# ChronoCape.net
KiCad netlist of a schematic drawn in EAGLE
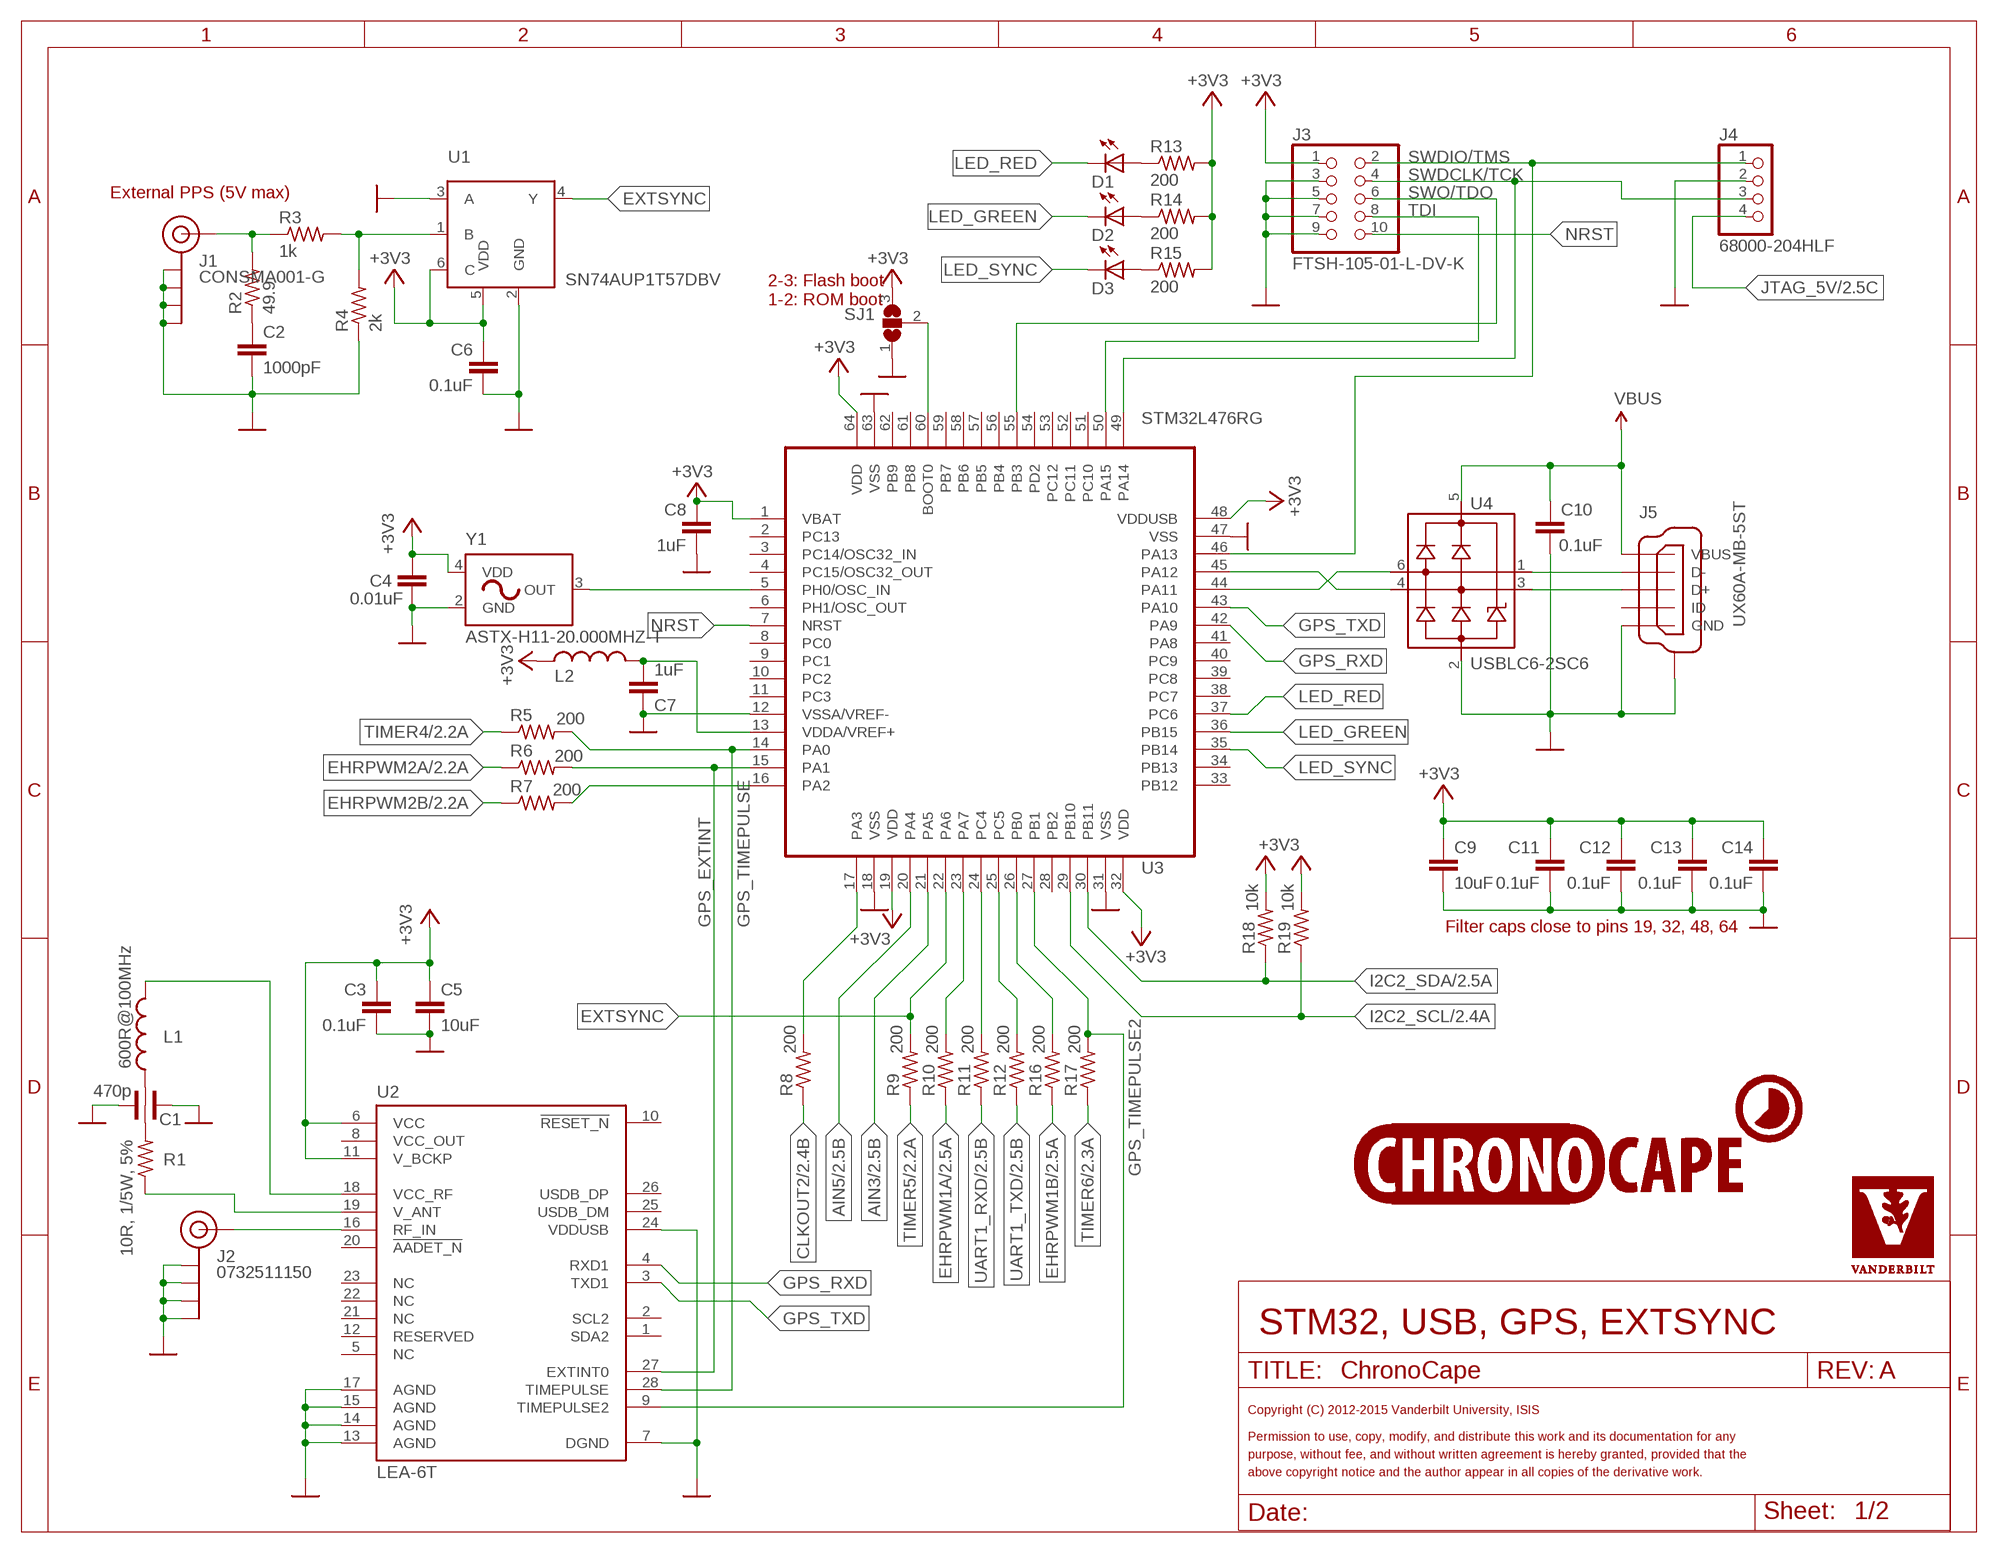
[diagram p0: schematic, sheet 1]
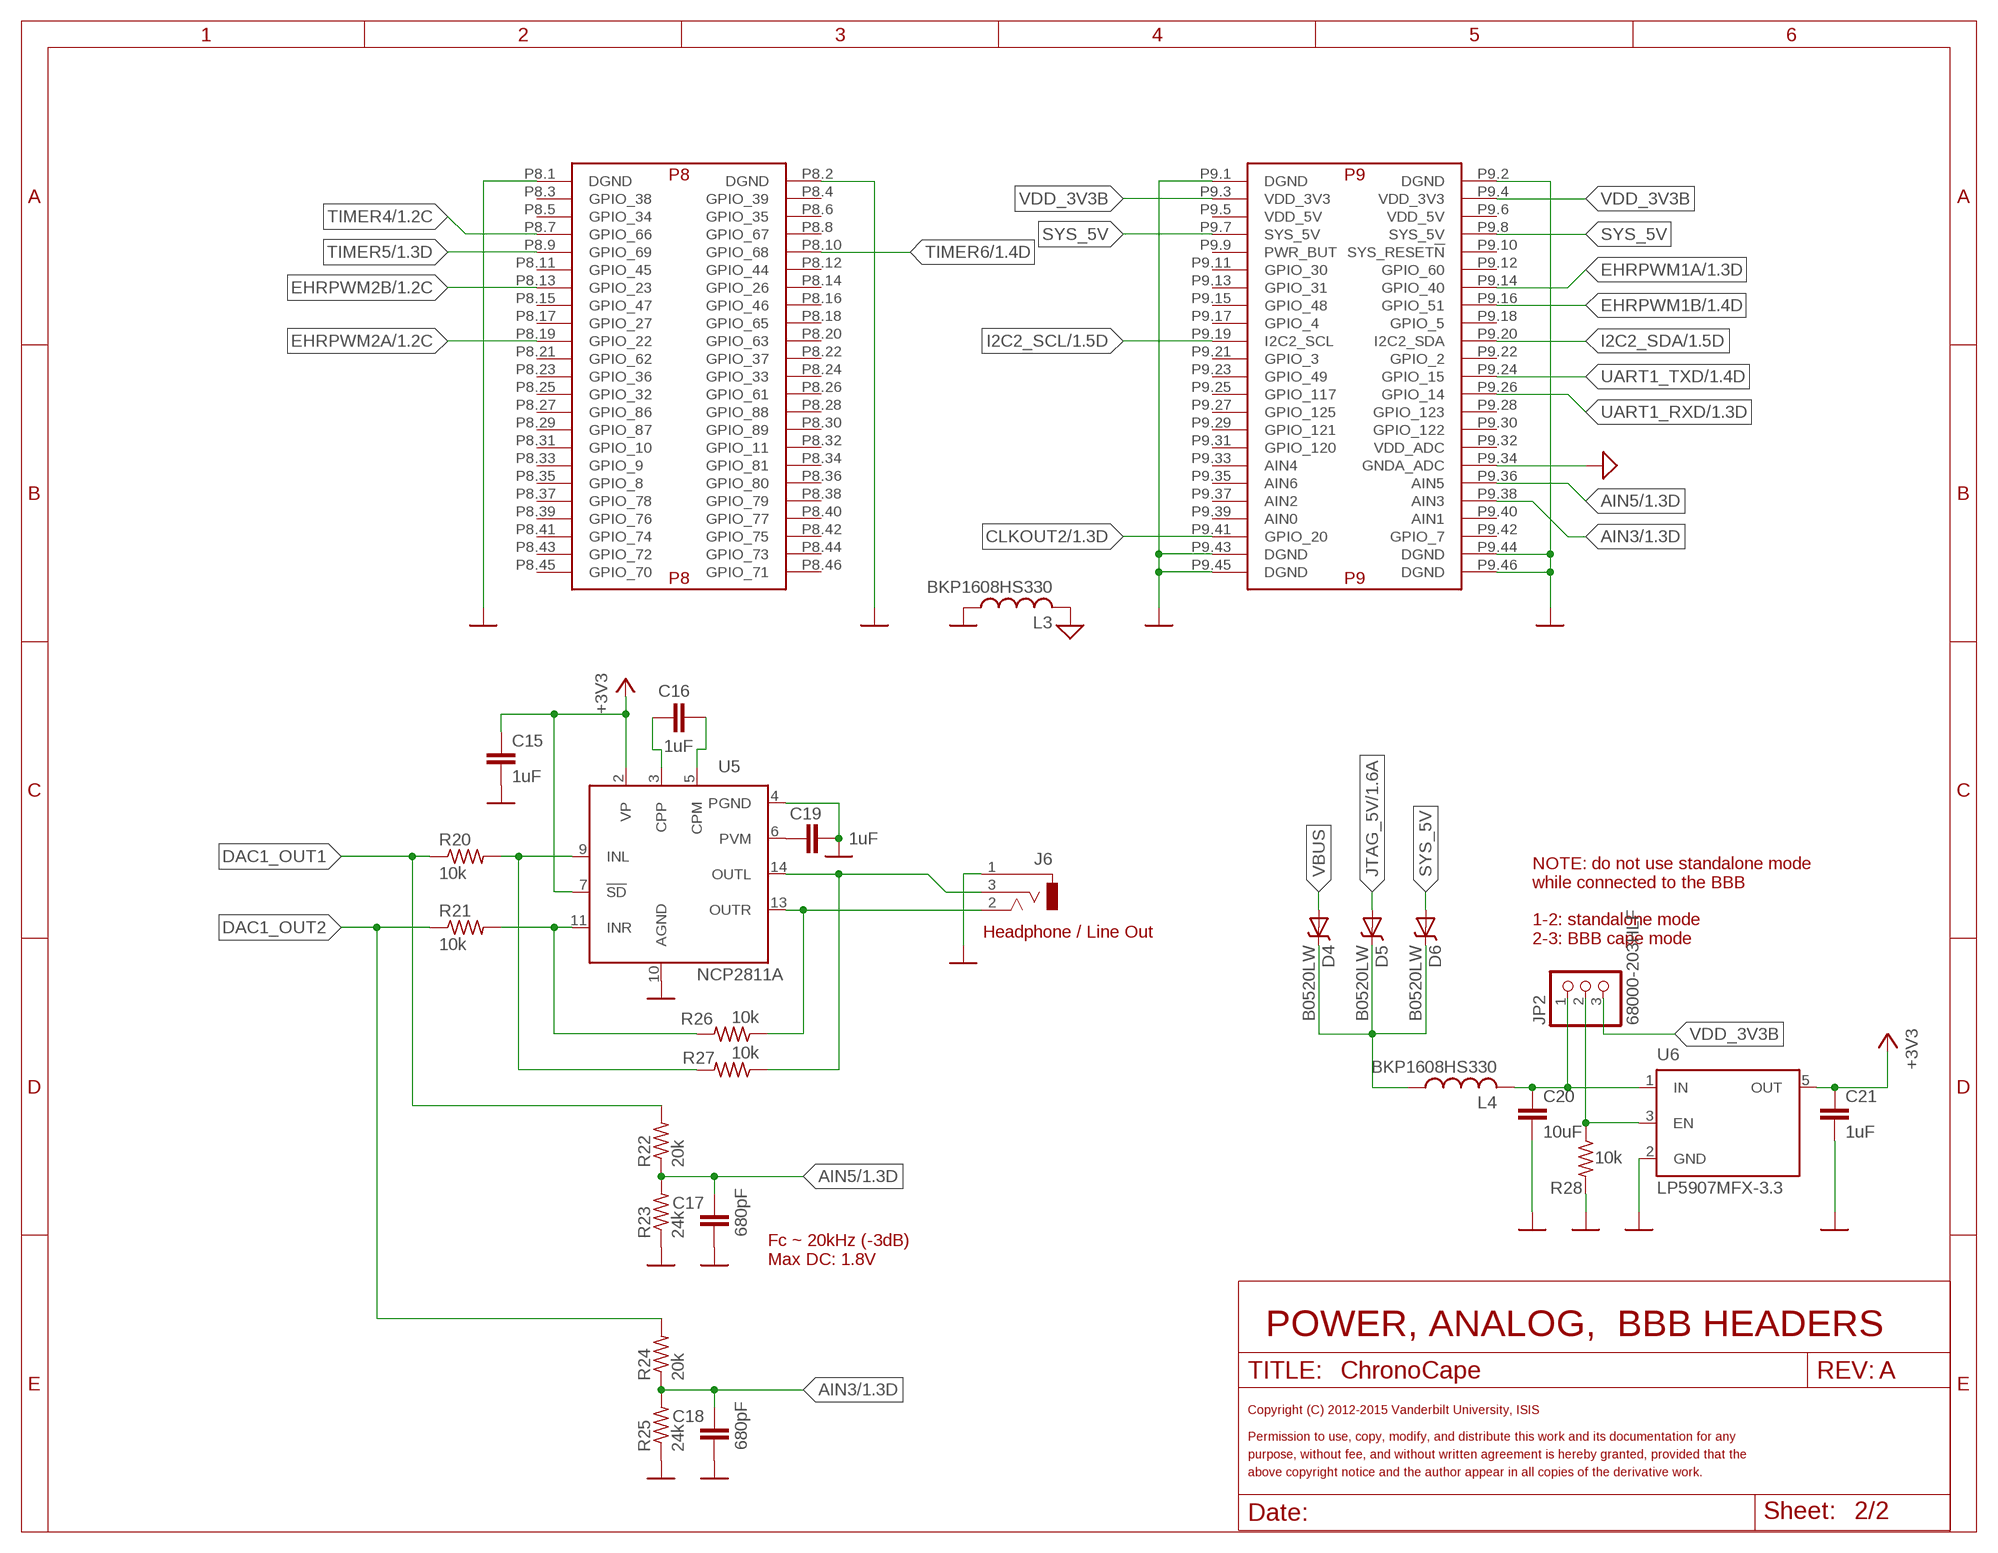
[diagram p1: schematic, sheet 2]

(export (version "E")
  (design (tool "Eeschema 10.0.6"))
  (components
    (comp (ref "C1")
      (value "470p")
      (footprint "eagle-import:CTHROUGH0805")
      (libsource (lib "eagle-import") (part "CTHROUGH0805"))
    )
    (comp (ref "C2")
      (value "1000pF")
      (footprint "eagle-import:CHIP0603")
      (libsource (lib "eagle-import") (part "C0603"))
    )
    (comp (ref "C3")
      (value "0.1uF")
      (footprint "eagle-import:CHIP0603")
      (libsource (lib "eagle-import") (part "C0603"))
    )
    (comp (ref "C4")
      (value "0.01uF")
      (footprint "eagle-import:CHIP0603")
      (libsource (lib "eagle-import") (part "C0603"))
    )
    (comp (ref "C5")
      (value "10uF")
      (footprint "eagle-import:CHIP0805")
      (libsource (lib "eagle-import") (part "C0805"))
    )
    (comp (ref "C6")
      (value "0.1uF")
      (footprint "eagle-import:CHIP0603")
      (libsource (lib "eagle-import") (part "C0603"))
    )
    (comp (ref "C7")
      (value "1uF")
      (footprint "eagle-import:CHIP0603")
      (libsource (lib "eagle-import") (part "C0603"))
    )
    (comp (ref "C8")
      (value "1uF")
      (footprint "eagle-import:CHIP0603")
      (libsource (lib "eagle-import") (part "C0603"))
    )
    (comp (ref "C9")
      (value "10uF")
      (footprint "eagle-import:CHIP0805")
      (libsource (lib "eagle-import") (part "C0805"))
    )
    (comp (ref "C10")
      (value "0.1uF")
      (footprint "eagle-import:CHIP0603")
      (libsource (lib "eagle-import") (part "C0603"))
    )
    (comp (ref "C11")
      (value "0.1uF")
      (footprint "eagle-import:CHIP0603")
      (libsource (lib "eagle-import") (part "C0603"))
    )
    (comp (ref "C12")
      (value "0.1uF")
      (footprint "eagle-import:CHIP0603")
      (libsource (lib "eagle-import") (part "C0603"))
    )
    (comp (ref "C13")
      (value "0.1uF")
      (footprint "eagle-import:CHIP0603")
      (libsource (lib "eagle-import") (part "C0603"))
    )
    (comp (ref "C14")
      (value "0.1uF")
      (footprint "eagle-import:CHIP0603")
      (libsource (lib "eagle-import") (part "C0603"))
    )
    (comp (ref "D1")
      (value "598-8010-107F")
      (footprint "eagle-import:D0603")
      (libsource (lib "eagle-import") (part "LED0603"))
    )
    (comp (ref "D2")
      (value "598-8070-107F")
      (footprint "eagle-import:D0603")
      (libsource (lib "eagle-import") (part "LED0603"))
    )
    (comp (ref "D3")
      (value "598-8030-107F")
      (footprint "eagle-import:D0603")
      (libsource (lib "eagle-import") (part "LED0603"))
    )
    (comp (ref "J1")
      (value "CONSMA001-G")
      (footprint "eagle-import:SMA-THROUGH")
      (libsource (lib "eagle-import") (part "SMA_THROUGH"))
    )
    (comp (ref "J2")
      (value "0732511150")
      (footprint "eagle-import:SMA-EDGE")
      (libsource (lib "eagle-import") (part "SMA_EDGE"))
    )
    (comp (ref "J3")
      (value "FTSH-105-01-L-DV-K")
      (footprint "eagle-import:FTSH-105-01-L-DV-K")
      (libsource (lib "eagle-import") (part "FTSH-105-01-L-DV-K"))
    )
    (comp (ref "J4")
      (value "68000-204HLF")
      (footprint "eagle-import:1X04")
      (libsource (lib "eagle-import") (part "PINHD-1X4"))
    )
    (comp (ref "J5")
      (value "UX60A-MB-5ST")
      (footprint "eagle-import:UX60A-MB-5ST")
      (libsource (lib "eagle-import") (part "UX60A-MB-5ST"))
    )
    (comp (ref "L1")
      (value "600R@100MHz")
      (footprint "eagle-import:CHIP0603")
      (libsource (lib "eagle-import") (part "L0603"))
    )
    (comp (ref "L2")
      (value "BKP1608HS330")
      (footprint "eagle-import:CHIP0603")
      (libsource (lib "eagle-import") (part "L0603"))
    )
    (comp (ref "LOGO1")
      (value "LOGO_CHRONOCAPE")
      (footprint "eagle-import:LOGO_CHRONOSCAPE")
      (libsource (lib "eagle-import") (part "LOGO_CHRONOCAPE"))
    )
    (comp (ref "LOGO2")
      (value "LOGO_VANDERBILT280MIL")
      (footprint "eagle-import:LOGO_VANDERBILT_280MIL")
      (libsource (lib "eagle-import") (part "LOGO_VANDERBILT280MIL"))
    )
    (comp (ref "R1")
      (value "10R, 1/5W, 5%")
      (footprint "eagle-import:CHIP0603")
      (libsource (lib "eagle-import") (part "R0603"))
    )
    (comp (ref "R2")
      (value "49.9")
      (footprint "eagle-import:CHIP0603")
      (libsource (lib "eagle-import") (part "R0603"))
    )
    (comp (ref "R3")
      (value "1k")
      (footprint "eagle-import:CHIP0603")
      (libsource (lib "eagle-import") (part "R0603"))
    )
    (comp (ref "R4")
      (value "2k")
      (footprint "eagle-import:CHIP0603")
      (libsource (lib "eagle-import") (part "R0603"))
    )
    (comp (ref "R5")
      (value "200")
      (footprint "eagle-import:CHIP0603")
      (libsource (lib "eagle-import") (part "R0603"))
    )
    (comp (ref "R6")
      (value "200")
      (footprint "eagle-import:CHIP0603")
      (libsource (lib "eagle-import") (part "R0603"))
    )
    (comp (ref "R7")
      (value "200")
      (footprint "eagle-import:CHIP0603")
      (libsource (lib "eagle-import") (part "R0603"))
    )
    (comp (ref "R8")
      (value "200")
      (footprint "eagle-import:CHIP0603")
      (libsource (lib "eagle-import") (part "R0603"))
    )
    (comp (ref "R9")
      (value "200")
      (footprint "eagle-import:CHIP0603")
      (libsource (lib "eagle-import") (part "R0603"))
    )
    (comp (ref "R10")
      (value "200")
      (footprint "eagle-import:CHIP0603")
      (libsource (lib "eagle-import") (part "R0603"))
    )
    (comp (ref "R11")
      (value "200")
      (footprint "eagle-import:CHIP0603")
      (libsource (lib "eagle-import") (part "R0603"))
    )
    (comp (ref "R12")
      (value "200")
      (footprint "eagle-import:CHIP0603")
      (libsource (lib "eagle-import") (part "R0603"))
    )
    (comp (ref "R13")
      (value "200")
      (footprint "eagle-import:CHIP0603")
      (libsource (lib "eagle-import") (part "R0603"))
    )
    (comp (ref "R14")
      (value "200")
      (footprint "eagle-import:CHIP0603")
      (libsource (lib "eagle-import") (part "R0603"))
    )
    (comp (ref "R15")
      (value "200")
      (footprint "eagle-import:CHIP0603")
      (libsource (lib "eagle-import") (part "R0603"))
    )
    (comp (ref "R16")
      (value "200")
      (footprint "eagle-import:CHIP0603")
      (libsource (lib "eagle-import") (part "R0603"))
    )
    (comp (ref "R17")
      (value "200")
      (footprint "eagle-import:CHIP0603")
      (libsource (lib "eagle-import") (part "R0603"))
    )
    (comp (ref "R18")
      (value "10k")
      (footprint "eagle-import:CHIP0603")
      (libsource (lib "eagle-import") (part "R0603"))
    )
    (comp (ref "R19")
      (value "10k")
      (footprint "eagle-import:CHIP0603")
      (libsource (lib "eagle-import") (part "R0603"))
    )
    (comp (ref "SJ1")
      (value "SOLDERJUMPER_2WAYPASTE1&2")
      (footprint "eagle-import:SJ_3_PASTE1&2")
      (libsource (lib "eagle-import") (part "SOLDERJUMPER_2WAYPASTE1&2"))
    )
    (comp (ref "U1")
      (value "SN74AUP1T57DBV")
      (footprint "eagle-import:SOT23-6")
      (libsource (lib "eagle-import") (part "SN74AUP1T57DBV"))
    )
    (comp (ref "U2")
      (value "LEA-6T")
      (footprint "eagle-import:LEA-6")
      (libsource (lib "eagle-import") (part "LEA-6T"))
    )
    (comp (ref "U3")
      (value "STM32L476RG")
      (footprint "eagle-import:LQFP64")
      (libsource (lib "eagle-import") (part "STM32L476RG"))
    )
    (comp (ref "U4")
      (value "USBLC6-2SC6")
      (footprint "eagle-import:SOT23-6L")
      (fields (field (name "MF") "STMicroelectronics"))
      (libsource (lib "eagle-import") (part "USBLC6-2SC6"))
    )
    (comp (ref "Y1")
      (value "ASTX-H11-20.000MHZ-T")
      (footprint "eagle-import:SMD_3.2X2.5")
      (libsource (lib "eagle-import") (part "OSC_ASTX-H11"))
    )
    (comp (ref "BBB1")
      (value "BEAGLE_BONE_BLACK_CAPE")
      (footprint "eagle-import:BEAGLE_BONE_BLACK_CAPE")
      (libsource (lib "eagle-import") (part "BEAGLE_BONE_BLACK_CAPE"))
    )
    (comp (ref "C15")
      (value "1uF")
      (footprint "eagle-import:CHIP0603")
      (libsource (lib "eagle-import") (part "C0603"))
    )
    (comp (ref "C16")
      (value "1uF")
      (footprint "eagle-import:CHIP0603")
      (libsource (lib "eagle-import") (part "C0603"))
    )
    (comp (ref "C17")
      (value "680pF")
      (footprint "eagle-import:CHIP0603")
      (libsource (lib "eagle-import") (part "C0603"))
    )
    (comp (ref "C18")
      (value "680pF")
      (footprint "eagle-import:CHIP0603")
      (libsource (lib "eagle-import") (part "C0603"))
    )
    (comp (ref "C19")
      (value "1uF")
      (footprint "eagle-import:CHIP0603")
      (libsource (lib "eagle-import") (part "C0603"))
    )
    (comp (ref "C20")
      (value "10uF")
      (footprint "eagle-import:CHIP0805")
      (libsource (lib "eagle-import") (part "C0805"))
    )
    (comp (ref "C21")
      (value "1uF")
      (footprint "eagle-import:CHIP0603")
      (libsource (lib "eagle-import") (part "C0603"))
    )
    (comp (ref "D4")
      (value "B0520LW")
      (footprint "eagle-import:SOD-123")
      (libsource (lib "eagle-import") (part "DIODE-SCHOTTKYSOD-123"))
    )
    (comp (ref "D5")
      (value "B0520LW")
      (footprint "eagle-import:SOD-123")
      (libsource (lib "eagle-import") (part "DIODE-SCHOTTKYSOD-123"))
    )
    (comp (ref "D6")
      (value "B0520LW")
      (footprint "eagle-import:SOD-123")
      (libsource (lib "eagle-import") (part "DIODE-SCHOTTKYSOD-123"))
    )
    (comp (ref "J6")
      (value "CON_STEREO_JACK_SJ-3523-SMT")
      (footprint "eagle-import:SJ-3523-SMT")
      (libsource (lib "eagle-import") (part "CON_STEREO_JACK_SJ-3523-SMT"))
    )
    (comp (ref "JP2")
      (value "68000-203HLF")
      (footprint "eagle-import:1X03")
      (libsource (lib "eagle-import") (part "PINHD-1X3"))
    )
    (comp (ref "L3")
      (value "BKP1608HS330")
      (footprint "eagle-import:CHIP0603")
      (libsource (lib "eagle-import") (part "L0603"))
    )
    (comp (ref "L4")
      (value "BKP1608HS330")
      (footprint "eagle-import:CHIP0603")
      (libsource (lib "eagle-import") (part "L0603"))
    )
    (comp (ref "R20")
      (value "10k")
      (footprint "eagle-import:CHIP0603")
      (libsource (lib "eagle-import") (part "R0603"))
    )
    (comp (ref "R21")
      (value "10k")
      (footprint "eagle-import:CHIP0603")
      (libsource (lib "eagle-import") (part "R0603"))
    )
    (comp (ref "R22")
      (value "20k")
      (footprint "eagle-import:CHIP0603")
      (libsource (lib "eagle-import") (part "R0603"))
    )
    (comp (ref "R23")
      (value "24k")
      (footprint "eagle-import:CHIP0603")
      (libsource (lib "eagle-import") (part "R0603"))
    )
    (comp (ref "R24")
      (value "20k")
      (footprint "eagle-import:CHIP0603")
      (libsource (lib "eagle-import") (part "R0603"))
    )
    (comp (ref "R25")
      (value "24k")
      (footprint "eagle-import:CHIP0603")
      (libsource (lib "eagle-import") (part "R0603"))
    )
    (comp (ref "R26")
      (value "10k")
      (footprint "eagle-import:CHIP0603")
      (libsource (lib "eagle-import") (part "R0603"))
    )
    (comp (ref "R27")
      (value "10k")
      (footprint "eagle-import:CHIP0603")
      (libsource (lib "eagle-import") (part "R0603"))
    )
    (comp (ref "R28")
      (value "10k")
      (footprint "eagle-import:CHIP0603")
      (libsource (lib "eagle-import") (part "R0603"))
    )
    (comp (ref "U5")
      (value "NCP2811A")
      (footprint "eagle-import:TSSOP14")
      (libsource (lib "eagle-import") (part "NCP2811A"))
    )
    (comp (ref "U6")
      (value "LP5907MFX-3.3")
      (footprint "eagle-import:SOT23-5")
      (libsource (lib "eagle-import") (part "LP5907MFX"))
    )
  )
  (nets
    (net (code "1") (name "+3V3") (class "Default")
      (node (ref "C11") (pin "1") (pinfunction "1_1") (pintype "passive"))
      (node (ref "C12") (pin "1") (pinfunction "1_1") (pintype "passive"))
      (node (ref "C13") (pin "1") (pinfunction "1_1") (pintype "passive"))
      (node (ref "C14") (pin "1") (pinfunction "1_1") (pintype "passive"))
      (node (ref "C15") (pin "1") (pinfunction "1_1") (pintype "passive"))
      (node (ref "C21") (pin "1") (pinfunction "1_1") (pintype "passive"))
      (node (ref "C3") (pin "1") (pinfunction "1_1") (pintype "passive"))
      (node (ref "C4") (pin "1") (pinfunction "1_1") (pintype "passive"))
      (node (ref "C5") (pin "1") (pinfunction "1_1") (pintype "passive"))
      (node (ref "C6") (pin "1") (pinfunction "1_1") (pintype "passive"))
      (node (ref "C8") (pin "1") (pinfunction "1_1") (pintype "passive"))
      (node (ref "C9") (pin "1") (pinfunction "1_1") (pintype "passive"))
      (node (ref "J3") (pin "1") (pinfunction "1_1") (pintype "passive"))
      (node (ref "L2") (pin "2") (pinfunction "2_2") (pintype "passive"))
      (node (ref "R13") (pin "2") (pinfunction "2_2") (pintype "passive"))
      (node (ref "R14") (pin "2") (pinfunction "2_2") (pintype "passive"))
      (node (ref "R15") (pin "2") (pinfunction "2_2") (pintype "passive"))
      (node (ref "R18") (pin "2") (pinfunction "2_2") (pintype "passive"))
      (node (ref "R19") (pin "2") (pinfunction "2_2") (pintype "passive"))
      (node (ref "SJ1") (pin "3") (pinfunction "3_3") (pintype "passive"))
      (node (ref "U1") (pin "5") (pinfunction "VDD_5") (pintype "power_in"))
      (node (ref "U1") (pin "6") (pinfunction "C_6") (pintype "input"))
      (node (ref "U2") (pin "11") (pinfunction "V_BCKP_11") (pintype "power_in"))
      (node (ref "U2") (pin "6") (pinfunction "VCC_6") (pintype "power_in"))
      (node (ref "U3") (pin "1") (pinfunction "VBAT_1") (pintype "power_in"))
      (node (ref "U3") (pin "19") (pinfunction "VDD_19") (pintype "power_in"))
      (node (ref "U3") (pin "32") (pinfunction "VDD_32") (pintype "power_in"))
      (node (ref "U3") (pin "48") (pinfunction "VDDUSB_48") (pintype "power_in"))
      (node (ref "U3") (pin "64") (pinfunction "VDD_64") (pintype "power_in"))
      (node (ref "U5") (pin "2") (pinfunction "VP_2") (pintype "power_in"))
      (node (ref "U5") (pin "7") (pinfunction "~{SD}_7") (pintype "input"))
      (node (ref "U6") (pin "5") (pinfunction "OUT_5") (pintype "power_in"))
      (node (ref "Y1") (pin "4") (pinfunction "VDD_4") (pintype "power_in"))
    )
    (net (code "2") (name "AGND") (class "Default")
      (node (ref "BBB1") (pin "P9.34") (pinfunction "GNDA_ADC_P9.34") (pintype "bidirectional"))
      (node (ref "L3") (pin "2") (pinfunction "2_2") (pintype "passive"))
    )
    (net (code "3") (name "AIN3") (class "Default")
      (node (ref "BBB1") (pin "P9.38") (pinfunction "AIN3_P9.38") (pintype "bidirectional"))
      (node (ref "C18") (pin "1") (pinfunction "1_1") (pintype "passive"))
      (node (ref "R24") (pin "1") (pinfunction "1_1") (pintype "passive"))
      (node (ref "R25") (pin "2") (pinfunction "2_2") (pintype "passive"))
      (node (ref "U3") (pin "21") (pinfunction "PA5_21") (pintype "bidirectional"))
    )
    (net (code "4") (name "AIN5") (class "Default")
      (node (ref "BBB1") (pin "P9.36") (pinfunction "AIN5_P9.36") (pintype "bidirectional"))
      (node (ref "C17") (pin "1") (pinfunction "1_1") (pintype "passive"))
      (node (ref "R22") (pin "1") (pinfunction "1_1") (pintype "passive"))
      (node (ref "R23") (pin "2") (pinfunction "2_2") (pintype "passive"))
      (node (ref "U3") (pin "20") (pinfunction "PA4_20") (pintype "bidirectional"))
    )
    (net (code "5") (name "CLKOUT2") (class "Default")
      (node (ref "BBB1") (pin "P9.41") (pinfunction "GPIO_20_P9.41") (pintype "bidirectional"))
      (node (ref "R8") (pin "1") (pinfunction "1_1") (pintype "passive"))
    )
    (net (code "6") (name "DAC1_OUT1") (class "Default")
      (node (ref "R20") (pin "1") (pinfunction "1_1") (pintype "passive"))
      (node (ref "R22") (pin "2") (pinfunction "2_2") (pintype "passive"))
    )
    (net (code "7") (name "DAC1_OUT2") (class "Default")
      (node (ref "R21") (pin "1") (pinfunction "1_1") (pintype "passive"))
      (node (ref "R24") (pin "2") (pinfunction "2_2") (pintype "passive"))
    )
    (net (code "8") (name "EHRPWM1A") (class "Default")
      (node (ref "BBB1") (pin "P9.14") (pinfunction "GPIO_40_P9.14") (pintype "bidirectional"))
      (node (ref "R10") (pin "1") (pinfunction "1_1") (pintype "passive"))
    )
    (net (code "9") (name "EHRPWM1B") (class "Default")
      (node (ref "BBB1") (pin "P9.16") (pinfunction "GPIO_51_P9.16") (pintype "bidirectional"))
      (node (ref "R16") (pin "1") (pinfunction "1_1") (pintype "passive"))
    )
    (net (code "10") (name "EHRPWM2A") (class "Default")
      (node (ref "BBB1") (pin "P8.19") (pinfunction "GPIO_22_P8.19") (pintype "bidirectional"))
      (node (ref "R6") (pin "1") (pinfunction "1_1") (pintype "passive"))
    )
    (net (code "11") (name "EHRPWM2B") (class "Default")
      (node (ref "BBB1") (pin "P8.13") (pinfunction "GPIO_23_P8.13") (pintype "bidirectional"))
      (node (ref "R7") (pin "1") (pinfunction "1_1") (pintype "passive"))
    )
    (net (code "12") (name "EXTSYNC") (class "Default")
      (node (ref "R9") (pin "2") (pinfunction "2_2") (pintype "passive"))
      (node (ref "U1") (pin "4") (pinfunction "Y_4") (pintype "output"))
      (node (ref "U3") (pin "22") (pinfunction "PA6_22") (pintype "bidirectional"))
    )
    (net (code "13") (name "GND") (class "Default")
      (node (ref "BBB1") (pin "P8.1") (pinfunction "DGND_P8.1") (pintype "bidirectional"))
      (node (ref "BBB1") (pin "P8.2") (pinfunction "DGND_P8.2") (pintype "bidirectional"))
      (node (ref "BBB1") (pin "P9.1") (pinfunction "DGND_P9.1") (pintype "bidirectional"))
      (node (ref "BBB1") (pin "P9.2") (pinfunction "DGND_P9.2") (pintype "bidirectional"))
      (node (ref "BBB1") (pin "P9.43") (pinfunction "DGND_P9.43") (pintype "bidirectional"))
      (node (ref "BBB1") (pin "P9.44") (pinfunction "DGND_P9.44") (pintype "bidirectional"))
      (node (ref "BBB1") (pin "P9.45") (pinfunction "DGND_P9.45") (pintype "bidirectional"))
      (node (ref "BBB1") (pin "P9.46") (pinfunction "DGND_P9.46") (pintype "bidirectional"))
      (node (ref "C1") (pin "GND$1") (pinfunction "GND_GND$1") (pintype "passive"))
      (node (ref "C1") (pin "GND$2") (pinfunction "GND_GND$2") (pintype "passive"))
      (node (ref "C10") (pin "2") (pinfunction "2_2") (pintype "passive"))
      (node (ref "C11") (pin "2") (pinfunction "2_2") (pintype "passive"))
      (node (ref "C12") (pin "2") (pinfunction "2_2") (pintype "passive"))
      (node (ref "C13") (pin "2") (pinfunction "2_2") (pintype "passive"))
      (node (ref "C14") (pin "2") (pinfunction "2_2") (pintype "passive"))
      (node (ref "C15") (pin "2") (pinfunction "2_2") (pintype "passive"))
      (node (ref "C17") (pin "2") (pinfunction "2_2") (pintype "passive"))
      (node (ref "C18") (pin "2") (pinfunction "2_2") (pintype "passive"))
      (node (ref "C19") (pin "2") (pinfunction "2_2") (pintype "passive"))
      (node (ref "C2") (pin "2") (pinfunction "2_2") (pintype "passive"))
      (node (ref "C20") (pin "2") (pinfunction "2_2") (pintype "passive"))
      (node (ref "C21") (pin "2") (pinfunction "2_2") (pintype "passive"))
      (node (ref "C3") (pin "2") (pinfunction "2_2") (pintype "passive"))
      (node (ref "C4") (pin "2") (pinfunction "2_2") (pintype "passive"))
      (node (ref "C5") (pin "2") (pinfunction "2_2") (pintype "passive"))
      (node (ref "C6") (pin "2") (pinfunction "2_2") (pintype "passive"))
      (node (ref "C7") (pin "1") (pinfunction "1_1") (pintype "passive"))
      (node (ref "C8") (pin "2") (pinfunction "2_2") (pintype "passive"))
      (node (ref "C9") (pin "2") (pinfunction "2_2") (pintype "passive"))
      (node (ref "J1") (pin "GND@0") (pinfunction "GND_GND@0") (pintype "bidirectional"))
      (node (ref "J1") (pin "GND@1") (pinfunction "GND_GND@1") (pintype "bidirectional"))
      (node (ref "J1") (pin "GND@2") (pinfunction "GND_GND@2") (pintype "bidirectional"))
      (node (ref "J1") (pin "GND@3") (pinfunction "GND_GND@3") (pintype "bidirectional"))
      (node (ref "J2") (pin "GND@0") (pinfunction "GND_GND@0") (pintype "bidirectional"))
      (node (ref "J2") (pin "GND@1") (pinfunction "GND_GND@1") (pintype "bidirectional"))
      (node (ref "J2") (pin "GND@2") (pinfunction "GND_GND@2") (pintype "bidirectional"))
      (node (ref "J2") (pin "GND@3") (pinfunction "GND_GND@3") (pintype "bidirectional"))
      (node (ref "J3") (pin "3") (pinfunction "3_3") (pintype "passive"))
      (node (ref "J3") (pin "5") (pinfunction "5_5") (pintype "passive"))
      (node (ref "J3") (pin "7") (pinfunction "7_7") (pintype "passive"))
      (node (ref "J3") (pin "9") (pinfunction "9_9") (pintype "passive"))
      (node (ref "J4") (pin "2") (pinfunction "2_2") (pintype "passive"))
      (node (ref "J5") (pin "5") (pinfunction "GND_5") (pintype "power_in"))
      (node (ref "J5") (pin "SHLD@1") (pinfunction "SHLD_SHLD@1") (pintype "passive"))
      (node (ref "J5") (pin "SHLD@2") (pinfunction "SHLD_SHLD@2") (pintype "passive"))
      (node (ref "J5") (pin "SHLD@3") (pinfunction "SHLD_SHLD@3") (pintype "passive"))
      (node (ref "J5") (pin "SHLD@4") (pinfunction "SHLD_SHLD@4") (pintype "passive"))
      (node (ref "J6") (pin "1") (pinfunction "1_1") (pintype "passive"))
      (node (ref "L3") (pin "1") (pinfunction "1_1") (pintype "passive"))
      (node (ref "R23") (pin "1") (pinfunction "1_1") (pintype "passive"))
      (node (ref "R25") (pin "1") (pinfunction "1_1") (pintype "passive"))
      (node (ref "R28") (pin "2") (pinfunction "2_2") (pintype "passive"))
      (node (ref "R4") (pin "1") (pinfunction "1_1") (pintype "passive"))
      (node (ref "SJ1") (pin "1") (pinfunction "1_1") (pintype "passive"))
      (node (ref "U1") (pin "2") (pinfunction "GND_2") (pintype "power_in"))
      (node (ref "U1") (pin "3") (pinfunction "A_3") (pintype "input"))
      (node (ref "U2") (pin "13") (pinfunction "AGND_13") (pintype "power_in"))
      (node (ref "U2") (pin "14") (pinfunction "AGND_14") (pintype "power_in"))
      (node (ref "U2") (pin "15") (pinfunction "AGND_15") (pintype "power_in"))
      (node (ref "U2") (pin "17") (pinfunction "AGND_17") (pintype "power_in"))
      (node (ref "U2") (pin "24") (pinfunction "VDDUSB_24") (pintype "power_in"))
      (node (ref "U2") (pin "7") (pinfunction "DGND_7") (pintype "power_in"))
      (node (ref "U3") (pin "12") (pinfunction "VSSA/VREF-_12") (pintype "power_in"))
      (node (ref "U3") (pin "18") (pinfunction "VSS_18") (pintype "power_in"))
      (node (ref "U3") (pin "31") (pinfunction "VSS_31") (pintype "power_in"))
      (node (ref "U3") (pin "47") (pinfunction "VSS_47") (pintype "power_in"))
      (node (ref "U3") (pin "63") (pinfunction "VSS_63") (pintype "power_in"))
      (node (ref "U4") (pin "2") (pinfunction "GND_2") (pintype "power_in"))
      (node (ref "U5") (pin "10") (pinfunction "AGND_10") (pintype "power_in"))
      (node (ref "U5") (pin "4") (pinfunction "PGND_4") (pintype "power_in"))
      (node (ref "U6") (pin "2") (pinfunction "GND_2") (pintype "power_in"))
      (node (ref "Y1") (pin "2") (pinfunction "GND_2") (pintype "power_in"))
    )
    (net (code "14") (name "GPS_EXTINT") (class "Default")
      (node (ref "R6") (pin "2") (pinfunction "2_2") (pintype "passive"))
      (node (ref "U2") (pin "27") (pinfunction "EXTINT0_27") (pintype "input"))
      (node (ref "U3") (pin "15") (pinfunction "PA1_15") (pintype "bidirectional"))
    )
    (net (code "15") (name "GPS_RXD") (class "Default")
      (node (ref "U2") (pin "4") (pinfunction "RXD1_4") (pintype "input"))
      (node (ref "U3") (pin "42") (pinfunction "PA9_42") (pintype "bidirectional"))
    )
    (net (code "16") (name "GPS_TIMEPULSE") (class "Default")
      (node (ref "R5") (pin "2") (pinfunction "2_2") (pintype "passive"))
      (node (ref "U2") (pin "28") (pinfunction "TIMEPULSE_28") (pintype "output"))
      (node (ref "U3") (pin "14") (pinfunction "PA0_14") (pintype "bidirectional"))
    )
    (net (code "17") (name "GPS_TIMEPULSE2") (class "Default")
      (node (ref "R17") (pin "2") (pinfunction "2_2") (pintype "passive"))
      (node (ref "U2") (pin "9") (pinfunction "TIMEPULSE2_9") (pintype "output"))
      (node (ref "U3") (pin "27") (pinfunction "PB1_27") (pintype "bidirectional"))
    )
    (net (code "18") (name "GPS_TXD") (class "Default")
      (node (ref "U2") (pin "3") (pinfunction "TXD1_3") (pintype "output"))
      (node (ref "U3") (pin "43") (pinfunction "PA10_43") (pintype "bidirectional"))
    )
    (net (code "19") (name "I2C2_SCL") (class "Default")
      (node (ref "BBB1") (pin "P9.19") (pinfunction "I2C2_SCL_P9.19") (pintype "bidirectional"))
      (node (ref "R19") (pin "1") (pinfunction "1_1") (pintype "passive"))
      (node (ref "U3") (pin "29") (pinfunction "PB10_29") (pintype "bidirectional"))
    )
    (net (code "20") (name "I2C2_SDA") (class "Default")
      (node (ref "BBB1") (pin "P9.20") (pinfunction "I2C2_SDA_P9.20") (pintype "bidirectional"))
      (node (ref "R18") (pin "1") (pinfunction "1_1") (pintype "passive"))
      (node (ref "U3") (pin "30") (pinfunction "PB11_30") (pintype "bidirectional"))
    )
    (net (code "21") (name "JTAG_5V") (class "Default")
      (node (ref "D5") (pin "A") (pinfunction "A_A") (pintype "passive"))
      (node (ref "J4") (pin "4") (pinfunction "4_4") (pintype "passive"))
    )
    (net (code "22") (name "LED_GREEN") (class "Default")
      (node (ref "D2") (pin "1") (pinfunction "C_1") (pintype "passive"))
      (node (ref "U3") (pin "36") (pinfunction "PB15_36") (pintype "bidirectional"))
    )
    (net (code "23") (name "LED_RED") (class "Default")
      (node (ref "D1") (pin "1") (pinfunction "C_1") (pintype "passive"))
      (node (ref "U3") (pin "37") (pinfunction "PC6_37") (pintype "bidirectional"))
    )
    (net (code "24") (name "LED_SYNC") (class "Default")
      (node (ref "D3") (pin "1") (pinfunction "C_1") (pintype "passive"))
      (node (ref "U3") (pin "35") (pinfunction "PB14_35") (pintype "bidirectional"))
    )
    (net (code "25") (name "NRST") (class "Default")
      (node (ref "J3") (pin "10") (pinfunction "10_10") (pintype "passive"))
      (node (ref "U3") (pin "7") (pinfunction "NRST_7") (pintype "input"))
    )
    (net (code "26") (name "Net-(C1-Pad1)") (class "Default")
      (node (ref "C1") (pin "1") (pinfunction "1_1") (pintype "passive"))
      (node (ref "R1") (pin "2") (pinfunction "2_2") (pintype "passive"))
    )
    (net (code "27") (name "Net-(C1-Pad2)") (class "Default")
      (node (ref "C1") (pin "2") (pinfunction "2_2") (pintype "passive"))
      (node (ref "L1") (pin "1") (pinfunction "1_1") (pintype "passive"))
    )
    (net (code "28") (name "Net-(C2-Pad1)") (class "Default")
      (node (ref "C2") (pin "1") (pinfunction "1_1") (pintype "passive"))
      (node (ref "R2") (pin "1") (pinfunction "1_1") (pintype "passive"))
    )
    (net (code "29") (name "Net-(D1-A)") (class "Default")
      (node (ref "D1") (pin "2") (pinfunction "A_2") (pintype "passive"))
      (node (ref "R13") (pin "1") (pinfunction "1_1") (pintype "passive"))
    )
    (net (code "30") (name "Net-(D2-A)") (class "Default")
      (node (ref "D2") (pin "2") (pinfunction "A_2") (pintype "passive"))
      (node (ref "R14") (pin "1") (pinfunction "1_1") (pintype "passive"))
    )
    (net (code "31") (name "Net-(D3-A)") (class "Default")
      (node (ref "D3") (pin "2") (pinfunction "A_2") (pintype "passive"))
      (node (ref "R15") (pin "1") (pinfunction "1_1") (pintype "passive"))
    )
    (net (code "32") (name "Net-(D4-PadC)") (class "Default")
      (node (ref "D4") (pin "C") (pinfunction "C_C") (pintype "passive"))
      (node (ref "D5") (pin "C") (pinfunction "C_C") (pintype "passive"))
      (node (ref "D6") (pin "C") (pinfunction "C_C") (pintype "passive"))
      (node (ref "L4") (pin "1") (pinfunction "1_1") (pintype "passive"))
    )
    (net (code "33") (name "Net-(J1-SIGNAL)") (class "Default")
      (node (ref "J1") (pin "SIG") (pinfunction "SIGNAL_SIG") (pintype "bidirectional"))
      (node (ref "R2") (pin "2") (pinfunction "2_2") (pintype "passive"))
      (node (ref "R3") (pin "1") (pinfunction "1_1") (pintype "passive"))
    )
    (net (code "34") (name "Net-(J2-SIGNAL)") (class "Default")
      (node (ref "J2") (pin "SIG") (pinfunction "SIGNAL_SIG") (pintype "bidirectional"))
      (node (ref "U2") (pin "16") (pinfunction "RF_IN_16") (pintype "tri_state"))
    )
    (net (code "35") (name "Net-(J5-D+)") (class "Default")
      (node (ref "J5") (pin "3") (pinfunction "D+_3") (pintype "bidirectional"))
      (node (ref "U4") (pin "3") (pinfunction "IO2_3") (pintype "bidirectional"))
    )
    (net (code "36") (name "Net-(J5-D-)") (class "Default")
      (node (ref "J5") (pin "2") (pinfunction "D-_2") (pintype "bidirectional"))
      (node (ref "U4") (pin "1") (pinfunction "IO1_1") (pintype "bidirectional"))
    )
    (net (code "37") (name "Net-(U1-B)") (class "Default")
      (node (ref "R3") (pin "2") (pinfunction "2_2") (pintype "passive"))
      (node (ref "R4") (pin "2") (pinfunction "2_2") (pintype "passive"))
      (node (ref "U1") (pin "1") (pinfunction "B_1") (pintype "input"))
    )
    (net (code "38") (name "Net-(U2-VCC_RF)") (class "Default")
      (node (ref "L1") (pin "2") (pinfunction "2_2") (pintype "passive"))
      (node (ref "U2") (pin "18") (pinfunction "VCC_RF_18") (pintype "power_in"))
    )
    (net (code "39") (name "Net-(U2-V_ANT)") (class "Default")
      (node (ref "R1") (pin "1") (pinfunction "1_1") (pintype "passive"))
      (node (ref "U2") (pin "19") (pinfunction "V_ANT_19") (pintype "input"))
    )
    (net (code "40") (name "Net-(U3-BOOT0)") (class "Default")
      (node (ref "SJ1") (pin "2") (pinfunction "2_2") (pintype "passive"))
      (node (ref "U3") (pin "60") (pinfunction "BOOT0_60") (pintype "input"))
    )
    (net (code "41") (name "Net-(U3-PA2)") (class "Default")
      (node (ref "R7") (pin "2") (pinfunction "2_2") (pintype "passive"))
      (node (ref "U3") (pin "16") (pinfunction "PA2_16") (pintype "bidirectional"))
    )
    (net (code "42") (name "Net-(U3-PA3)") (class "Default")
      (node (ref "R8") (pin "2") (pinfunction "2_2") (pintype "passive"))
      (node (ref "U3") (pin "17") (pinfunction "PA3_17") (pintype "bidirectional"))
    )
    (net (code "43") (name "Net-(U3-PA7)") (class "Default")
      (node (ref "R10") (pin "2") (pinfunction "2_2") (pintype "passive"))
      (node (ref "U3") (pin "23") (pinfunction "PA7_23") (pintype "bidirectional"))
    )
    (net (code "44") (name "Net-(U3-PA11)") (class "Default")
      (node (ref "U3") (pin "44") (pinfunction "PA11_44") (pintype "bidirectional"))
      (node (ref "U4") (pin "6") (pinfunction "IO1_6") (pintype "bidirectional"))
    )
    (net (code "45") (name "Net-(U3-PA12)") (class "Default")
      (node (ref "U3") (pin "45") (pinfunction "PA12_45") (pintype "bidirectional"))
      (node (ref "U4") (pin "4") (pinfunction "IO2_4") (pintype "bidirectional"))
    )
    (net (code "46") (name "Net-(U3-PB0)") (class "Default")
      (node (ref "R16") (pin "2") (pinfunction "2_2") (pintype "passive"))
      (node (ref "U3") (pin "26") (pinfunction "PB0_26") (pintype "bidirectional"))
    )
    (net (code "47") (name "Net-(U3-PC4)") (class "Default")
      (node (ref "R11") (pin "2") (pinfunction "2_2") (pintype "passive"))
      (node (ref "U3") (pin "24") (pinfunction "PC4_24") (pintype "bidirectional"))
    )
    (net (code "48") (name "Net-(U3-PC5)") (class "Default")
      (node (ref "R12") (pin "2") (pinfunction "2_2") (pintype "passive"))
      (node (ref "U3") (pin "25") (pinfunction "PC5_25") (pintype "bidirectional"))
    )
    (net (code "49") (name "Net-(U3-PH0{slash}OSC_IN)") (class "Default")
      (node (ref "U3") (pin "5") (pinfunction "PH0/OSC_IN_5") (pintype "bidirectional"))
      (node (ref "Y1") (pin "3") (pinfunction "OUT_3") (pintype "power_in"))
    )
    (net (code "50") (name "Net-(U3-VDDA{slash}VREF+)") (class "Default")
      (node (ref "C7") (pin "2") (pinfunction "2_2") (pintype "passive"))
      (node (ref "L2") (pin "1") (pinfunction "1_1") (pintype "passive"))
      (node (ref "U3") (pin "13") (pinfunction "VDDA/VREF+_13") (pintype "power_in"))
    )
    (net (code "51") (name "Net-(U5-CPM)") (class "Default")
      (node (ref "C16") (pin "2") (pinfunction "2_2") (pintype "passive"))
      (node (ref "U5") (pin "5") (pinfunction "CPM_5") (pintype "passive"))
    )
    (net (code "52") (name "Net-(U5-CPP)") (class "Default")
      (node (ref "C16") (pin "1") (pinfunction "1_1") (pintype "passive"))
      (node (ref "U5") (pin "3") (pinfunction "CPP_3") (pintype "passive"))
    )
    (net (code "53") (name "Net-(U5-INL)") (class "Default")
      (node (ref "R20") (pin "2") (pinfunction "2_2") (pintype "passive"))
      (node (ref "R27") (pin "2") (pinfunction "2_2") (pintype "passive"))
      (node (ref "U5") (pin "9") (pinfunction "INL_9") (pintype "tri_state"))
    )
    (net (code "54") (name "Net-(U5-INR)") (class "Default")
      (node (ref "R21") (pin "2") (pinfunction "2_2") (pintype "passive"))
      (node (ref "R26") (pin "2") (pinfunction "2_2") (pintype "passive"))
      (node (ref "U5") (pin "11") (pinfunction "INR_11") (pintype "tri_state"))
    )
    (net (code "55") (name "Net-(U5-OUTL)") (class "Default")
      (node (ref "J6") (pin "3") (pinfunction "3_3") (pintype "passive"))
      (node (ref "R27") (pin "1") (pinfunction "1_1") (pintype "passive"))
      (node (ref "U5") (pin "14") (pinfunction "OUTL_14") (pintype "passive"))
    )
    (net (code "56") (name "Net-(U5-OUTR)") (class "Default")
      (node (ref "J6") (pin "2") (pinfunction "2_2") (pintype "passive"))
      (node (ref "R26") (pin "1") (pinfunction "1_1") (pintype "passive"))
      (node (ref "U5") (pin "13") (pinfunction "OUTR_13") (pintype "passive"))
    )
    (net (code "57") (name "Net-(U5-PVM)") (class "Default")
      (node (ref "C19") (pin "1") (pinfunction "1_1") (pintype "passive"))
      (node (ref "U5") (pin "6") (pinfunction "PVM_6") (pintype "power_in"))
    )
    (net (code "58") (name "Net-(U6-EN)") (class "Default")
      (node (ref "JP2") (pin "2") (pinfunction "2_2") (pintype "passive"))
      (node (ref "R28") (pin "1") (pinfunction "1_1") (pintype "passive"))
      (node (ref "U6") (pin "3") (pinfunction "EN_3") (pintype "input"))
    )
    (net (code "59") (name "Net-(U6-IN)") (class "Default")
      (node (ref "C20") (pin "1") (pinfunction "1_1") (pintype "passive"))
      (node (ref "JP2") (pin "1") (pinfunction "1_1") (pintype "passive"))
      (node (ref "L4") (pin "2") (pinfunction "2_2") (pintype "passive"))
      (node (ref "U6") (pin "1") (pinfunction "IN_1") (pintype "power_in"))
    )
    (net (code "60") (name "SWDCLK{slash}TCK") (class "Default")
      (node (ref "J3") (pin "4") (pinfunction "4_4") (pintype "passive"))
      (node (ref "J4") (pin "3") (pinfunction "3_3") (pintype "passive"))
      (node (ref "U3") (pin "49") (pinfunction "PA14_49") (pintype "bidirectional"))
    )
    (net (code "61") (name "SWDIO{slash}TMS") (class "Default")
      (node (ref "J3") (pin "2") (pinfunction "2_2") (pintype "passive"))
      (node (ref "J4") (pin "1") (pinfunction "1_1") (pintype "passive"))
      (node (ref "U3") (pin "46") (pinfunction "PA13_46") (pintype "bidirectional"))
    )
    (net (code "62") (name "SWO{slash}TDO") (class "Default")
      (node (ref "J3") (pin "6") (pinfunction "6_6") (pintype "passive"))
      (node (ref "U3") (pin "55") (pinfunction "PB3_55") (pintype "bidirectional"))
    )
    (net (code "63") (name "SYS_5V") (class "Default")
      (node (ref "BBB1") (pin "P9.7") (pinfunction "SYS_5V_P9.7") (pintype "bidirectional"))
      (node (ref "BBB1") (pin "P9.8") (pinfunction "SYS_5V_P9.8") (pintype "bidirectional"))
      (node (ref "D6") (pin "A") (pinfunction "A_A") (pintype "passive"))
    )
    (net (code "64") (name "TDI") (class "Default")
      (node (ref "J3") (pin "8") (pinfunction "8_8") (pintype "passive"))
      (node (ref "U3") (pin "50") (pinfunction "PA15_50") (pintype "bidirectional"))
    )
    (net (code "65") (name "TIMER4") (class "Default")
      (node (ref "BBB1") (pin "P8.7") (pinfunction "GPIO_66_P8.7") (pintype "bidirectional"))
      (node (ref "R5") (pin "1") (pinfunction "1_1") (pintype "passive"))
    )
    (net (code "66") (name "TIMER5") (class "Default")
      (node (ref "BBB1") (pin "P8.9") (pinfunction "GPIO_69_P8.9") (pintype "bidirectional"))
      (node (ref "R9") (pin "1") (pinfunction "1_1") (pintype "passive"))
    )
    (net (code "67") (name "TIMER6") (class "Default")
      (node (ref "BBB1") (pin "P8.10") (pinfunction "GPIO_68_P8.10") (pintype "bidirectional"))
      (node (ref "R17") (pin "1") (pinfunction "1_1") (pintype "passive"))
    )
    (net (code "68") (name "UART1_RXD") (class "Default")
      (node (ref "BBB1") (pin "P9.26") (pinfunction "GPIO_14_P9.26") (pintype "bidirectional"))
      (node (ref "R11") (pin "1") (pinfunction "1_1") (pintype "passive"))
    )
    (net (code "69") (name "UART1_TXD") (class "Default")
      (node (ref "BBB1") (pin "P9.24") (pinfunction "GPIO_15_P9.24") (pintype "bidirectional"))
      (node (ref "R12") (pin "1") (pinfunction "1_1") (pintype "passive"))
    )
    (net (code "70") (name "VBUS") (class "Default")
      (node (ref "C10") (pin "1") (pinfunction "1_1") (pintype "passive"))
      (node (ref "D4") (pin "A") (pinfunction "A_A") (pintype "passive"))
      (node (ref "J5") (pin "1") (pinfunction "VBUS_1") (pintype "power_in"))
      (node (ref "U4") (pin "5") (pinfunction "VBUS_5") (pintype "power_in"))
    )
    (net (code "71") (name "VCC_OUT") (class "Default")
      (node (ref "U2") (pin "8") (pinfunction "VCC_OUT_8") (pintype "power_in"))
    )
    (net (code "72") (name "VDD_3V3B") (class "Default")
      (node (ref "BBB1") (pin "P9.3") (pinfunction "VDD_3V3_P9.3") (pintype "bidirectional"))
      (node (ref "BBB1") (pin "P9.4") (pinfunction "VDD_3V3_P9.4") (pintype "bidirectional"))
      (node (ref "JP2") (pin "3") (pinfunction "3_3") (pintype "passive"))
    )
    (net (code "73") (name "unconnected-(BBB1A-GPIO_8-PadP8.35)") (class "Default")
      (node (ref "BBB1") (pin "P8.35") (pinfunction "GPIO_8_P8.35") (pintype "bidirectional"))
    )
    (net (code "74") (name "unconnected-(BBB1A-GPIO_9-PadP8.33)") (class "Default")
      (node (ref "BBB1") (pin "P8.33") (pinfunction "GPIO_9_P8.33") (pintype "bidirectional"))
    )
    (net (code "75") (name "unconnected-(BBB1A-GPIO_10-PadP8.31)") (class "Default")
      (node (ref "BBB1") (pin "P8.31") (pinfunction "GPIO_10_P8.31") (pintype "bidirectional"))
    )
    (net (code "76") (name "unconnected-(BBB1A-GPIO_11-PadP8.32)") (class "Default")
      (node (ref "BBB1") (pin "P8.32") (pinfunction "GPIO_11_P8.32") (pintype "bidirectional"))
    )
    (net (code "77") (name "unconnected-(BBB1A-GPIO_26-PadP8.14)") (class "Default")
      (node (ref "BBB1") (pin "P8.14") (pinfunction "GPIO_26_P8.14") (pintype "bidirectional"))
    )
    (net (code "78") (name "unconnected-(BBB1A-GPIO_27-PadP8.17)") (class "Default")
      (node (ref "BBB1") (pin "P8.17") (pinfunction "GPIO_27_P8.17") (pintype "bidirectional"))
    )
    (net (code "79") (name "unconnected-(BBB1A-GPIO_32-PadP8.25)") (class "Default")
      (node (ref "BBB1") (pin "P8.25") (pinfunction "GPIO_32_P8.25") (pintype "bidirectional"))
    )
    (net (code "80") (name "unconnected-(BBB1A-GPIO_33-PadP8.24)") (class "Default")
      (node (ref "BBB1") (pin "P8.24") (pinfunction "GPIO_33_P8.24") (pintype "bidirectional"))
    )
    (net (code "81") (name "unconnected-(BBB1A-GPIO_34-PadP8.5)") (class "Default")
      (node (ref "BBB1") (pin "P8.5") (pinfunction "GPIO_34_P8.5") (pintype "bidirectional"))
    )
    (net (code "82") (name "unconnected-(BBB1A-GPIO_35-PadP8.6)") (class "Default")
      (node (ref "BBB1") (pin "P8.6") (pinfunction "GPIO_35_P8.6") (pintype "bidirectional"))
    )
    (net (code "83") (name "unconnected-(BBB1A-GPIO_36-PadP8.23)") (class "Default")
      (node (ref "BBB1") (pin "P8.23") (pinfunction "GPIO_36_P8.23") (pintype "bidirectional"))
    )
    (net (code "84") (name "unconnected-(BBB1A-GPIO_37-PadP8.22)") (class "Default")
      (node (ref "BBB1") (pin "P8.22") (pinfunction "GPIO_37_P8.22") (pintype "bidirectional"))
    )
    (net (code "85") (name "unconnected-(BBB1A-GPIO_38-PadP8.3)") (class "Default")
      (node (ref "BBB1") (pin "P8.3") (pinfunction "GPIO_38_P8.3") (pintype "bidirectional"))
    )
    (net (code "86") (name "unconnected-(BBB1A-GPIO_39-PadP8.4)") (class "Default")
      (node (ref "BBB1") (pin "P8.4") (pinfunction "GPIO_39_P8.4") (pintype "bidirectional"))
    )
    (net (code "87") (name "unconnected-(BBB1A-GPIO_44-PadP8.12)") (class "Default")
      (node (ref "BBB1") (pin "P8.12") (pinfunction "GPIO_44_P8.12") (pintype "bidirectional"))
    )
    (net (code "88") (name "unconnected-(BBB1A-GPIO_45-PadP8.11)") (class "Default")
      (node (ref "BBB1") (pin "P8.11") (pinfunction "GPIO_45_P8.11") (pintype "bidirectional"))
    )
    (net (code "89") (name "unconnected-(BBB1A-GPIO_46-PadP8.16)") (class "Default")
      (node (ref "BBB1") (pin "P8.16") (pinfunction "GPIO_46_P8.16") (pintype "bidirectional"))
    )
    (net (code "90") (name "unconnected-(BBB1A-GPIO_47-PadP8.15)") (class "Default")
      (node (ref "BBB1") (pin "P8.15") (pinfunction "GPIO_47_P8.15") (pintype "bidirectional"))
    )
    (net (code "91") (name "unconnected-(BBB1A-GPIO_61-PadP8.26)") (class "Default")
      (node (ref "BBB1") (pin "P8.26") (pinfunction "GPIO_61_P8.26") (pintype "bidirectional"))
    )
    (net (code "92") (name "unconnected-(BBB1A-GPIO_62-PadP8.21)") (class "Default")
      (node (ref "BBB1") (pin "P8.21") (pinfunction "GPIO_62_P8.21") (pintype "bidirectional"))
    )
    (net (code "93") (name "unconnected-(BBB1A-GPIO_63-PadP8.20)") (class "Default")
      (node (ref "BBB1") (pin "P8.20") (pinfunction "GPIO_63_P8.20") (pintype "bidirectional"))
    )
    (net (code "94") (name "unconnected-(BBB1A-GPIO_65-PadP8.18)") (class "Default")
      (node (ref "BBB1") (pin "P8.18") (pinfunction "GPIO_65_P8.18") (pintype "bidirectional"))
    )
    (net (code "95") (name "unconnected-(BBB1A-GPIO_67-PadP8.8)") (class "Default")
      (node (ref "BBB1") (pin "P8.8") (pinfunction "GPIO_67_P8.8") (pintype "bidirectional"))
    )
    (net (code "96") (name "unconnected-(BBB1A-GPIO_70-PadP8.45)") (class "Default")
      (node (ref "BBB1") (pin "P8.45") (pinfunction "GPIO_70_P8.45") (pintype "bidirectional"))
    )
    (net (code "97") (name "unconnected-(BBB1A-GPIO_71-PadP8.46)") (class "Default")
      (node (ref "BBB1") (pin "P8.46") (pinfunction "GPIO_71_P8.46") (pintype "bidirectional"))
    )
    (net (code "98") (name "unconnected-(BBB1A-GPIO_72-PadP8.43)") (class "Default")
      (node (ref "BBB1") (pin "P8.43") (pinfunction "GPIO_72_P8.43") (pintype "bidirectional"))
    )
    (net (code "99") (name "unconnected-(BBB1A-GPIO_73-PadP8.44)") (class "Default")
      (node (ref "BBB1") (pin "P8.44") (pinfunction "GPIO_73_P8.44") (pintype "bidirectional"))
    )
    (net (code "100") (name "unconnected-(BBB1A-GPIO_74-PadP8.41)") (class "Default")
      (node (ref "BBB1") (pin "P8.41") (pinfunction "GPIO_74_P8.41") (pintype "bidirectional"))
    )
    (net (code "101") (name "unconnected-(BBB1A-GPIO_75-PadP8.42)") (class "Default")
      (node (ref "BBB1") (pin "P8.42") (pinfunction "GPIO_75_P8.42") (pintype "bidirectional"))
    )
    (net (code "102") (name "unconnected-(BBB1A-GPIO_76-PadP8.39)") (class "Default")
      (node (ref "BBB1") (pin "P8.39") (pinfunction "GPIO_76_P8.39") (pintype "bidirectional"))
    )
    (net (code "103") (name "unconnected-(BBB1A-GPIO_77-PadP8.40)") (class "Default")
      (node (ref "BBB1") (pin "P8.40") (pinfunction "GPIO_77_P8.40") (pintype "bidirectional"))
    )
    (net (code "104") (name "unconnected-(BBB1A-GPIO_78-PadP8.37)") (class "Default")
      (node (ref "BBB1") (pin "P8.37") (pinfunction "GPIO_78_P8.37") (pintype "bidirectional"))
    )
    (net (code "105") (name "unconnected-(BBB1A-GPIO_79-PadP8.38)") (class "Default")
      (node (ref "BBB1") (pin "P8.38") (pinfunction "GPIO_79_P8.38") (pintype "bidirectional"))
    )
    (net (code "106") (name "unconnected-(BBB1A-GPIO_80-PadP8.36)") (class "Default")
      (node (ref "BBB1") (pin "P8.36") (pinfunction "GPIO_80_P8.36") (pintype "bidirectional"))
    )
    (net (code "107") (name "unconnected-(BBB1A-GPIO_81-PadP8.34)") (class "Default")
      (node (ref "BBB1") (pin "P8.34") (pinfunction "GPIO_81_P8.34") (pintype "bidirectional"))
    )
    (net (code "108") (name "unconnected-(BBB1A-GPIO_86-PadP8.27)") (class "Default")
      (node (ref "BBB1") (pin "P8.27") (pinfunction "GPIO_86_P8.27") (pintype "bidirectional"))
    )
    (net (code "109") (name "unconnected-(BBB1A-GPIO_87-PadP8.29)") (class "Default")
      (node (ref "BBB1") (pin "P8.29") (pinfunction "GPIO_87_P8.29") (pintype "bidirectional"))
    )
    (net (code "110") (name "unconnected-(BBB1A-GPIO_88-PadP8.28)") (class "Default")
      (node (ref "BBB1") (pin "P8.28") (pinfunction "GPIO_88_P8.28") (pintype "bidirectional"))
    )
    (net (code "111") (name "unconnected-(BBB1A-GPIO_89-PadP8.30)") (class "Default")
      (node (ref "BBB1") (pin "P8.30") (pinfunction "GPIO_89_P8.30") (pintype "bidirectional"))
    )
    (net (code "112") (name "unconnected-(BBB1B-AIN0-PadP9.39)") (class "Default")
      (node (ref "BBB1") (pin "P9.39") (pinfunction "AIN0_P9.39") (pintype "bidirectional"))
    )
    (net (code "113") (name "unconnected-(BBB1B-AIN1-PadP9.40)") (class "Default")
      (node (ref "BBB1") (pin "P9.40") (pinfunction "AIN1_P9.40") (pintype "bidirectional"))
    )
    (net (code "114") (name "unconnected-(BBB1B-AIN2-PadP9.37)") (class "Default")
      (node (ref "BBB1") (pin "P9.37") (pinfunction "AIN2_P9.37") (pintype "bidirectional"))
    )
    (net (code "115") (name "unconnected-(BBB1B-AIN4-PadP9.33)") (class "Default")
      (node (ref "BBB1") (pin "P9.33") (pinfunction "AIN4_P9.33") (pintype "bidirectional"))
    )
    (net (code "116") (name "unconnected-(BBB1B-AIN6-PadP9.35)") (class "Default")
      (node (ref "BBB1") (pin "P9.35") (pinfunction "AIN6_P9.35") (pintype "bidirectional"))
    )
    (net (code "117") (name "unconnected-(BBB1B-GPIO_2-PadP9.22)") (class "Default")
      (node (ref "BBB1") (pin "P9.22") (pinfunction "GPIO_2_P9.22") (pintype "bidirectional"))
    )
    (net (code "118") (name "unconnected-(BBB1B-GPIO_3-PadP9.21)") (class "Default")
      (node (ref "BBB1") (pin "P9.21") (pinfunction "GPIO_3_P9.21") (pintype "bidirectional"))
    )
    (net (code "119") (name "unconnected-(BBB1B-GPIO_4-PadP9.17)") (class "Default")
      (node (ref "BBB1") (pin "P9.17") (pinfunction "GPIO_4_P9.17") (pintype "bidirectional"))
    )
    (net (code "120") (name "unconnected-(BBB1B-GPIO_5-PadP9.18)") (class "Default")
      (node (ref "BBB1") (pin "P9.18") (pinfunction "GPIO_5_P9.18") (pintype "bidirectional"))
    )
    (net (code "121") (name "unconnected-(BBB1B-GPIO_7-PadP9.42)") (class "Default")
      (node (ref "BBB1") (pin "P9.42") (pinfunction "GPIO_7_P9.42") (pintype "bidirectional"))
    )
    (net (code "122") (name "unconnected-(BBB1B-GPIO_30-PadP9.11)") (class "Default")
      (node (ref "BBB1") (pin "P9.11") (pinfunction "GPIO_30_P9.11") (pintype "bidirectional"))
    )
    (net (code "123") (name "unconnected-(BBB1B-GPIO_31-PadP9.13)") (class "Default")
      (node (ref "BBB1") (pin "P9.13") (pinfunction "GPIO_31_P9.13") (pintype "bidirectional"))
    )
    (net (code "124") (name "unconnected-(BBB1B-GPIO_48-PadP9.15)") (class "Default")
      (node (ref "BBB1") (pin "P9.15") (pinfunction "GPIO_48_P9.15") (pintype "bidirectional"))
    )
    (net (code "125") (name "unconnected-(BBB1B-GPIO_49-PadP9.23)") (class "Default")
      (node (ref "BBB1") (pin "P9.23") (pinfunction "GPIO_49_P9.23") (pintype "bidirectional"))
    )
    (net (code "126") (name "unconnected-(BBB1B-GPIO_60-PadP9.12)") (class "Default")
      (node (ref "BBB1") (pin "P9.12") (pinfunction "GPIO_60_P9.12") (pintype "bidirectional"))
    )
    (net (code "127") (name "unconnected-(BBB1B-GPIO_117-PadP9.25)") (class "Default")
      (node (ref "BBB1") (pin "P9.25") (pinfunction "GPIO_117_P9.25") (pintype "bidirectional"))
    )
    (net (code "128") (name "unconnected-(BBB1B-GPIO_120-PadP9.31)") (class "Default")
      (node (ref "BBB1") (pin "P9.31") (pinfunction "GPIO_120_P9.31") (pintype "bidirectional"))
    )
    (net (code "129") (name "unconnected-(BBB1B-GPIO_121-PadP9.29)") (class "Default")
      (node (ref "BBB1") (pin "P9.29") (pinfunction "GPIO_121_P9.29") (pintype "bidirectional"))
    )
    (net (code "130") (name "unconnected-(BBB1B-GPIO_122-PadP9.30)") (class "Default")
      (node (ref "BBB1") (pin "P9.30") (pinfunction "GPIO_122_P9.30") (pintype "bidirectional"))
    )
    (net (code "131") (name "unconnected-(BBB1B-GPIO_123-PadP9.28)") (class "Default")
      (node (ref "BBB1") (pin "P9.28") (pinfunction "GPIO_123_P9.28") (pintype "bidirectional"))
    )
    (net (code "132") (name "unconnected-(BBB1B-GPIO_125-PadP9.27)") (class "Default")
      (node (ref "BBB1") (pin "P9.27") (pinfunction "GPIO_125_P9.27") (pintype "bidirectional"))
    )
    (net (code "133") (name "unconnected-(BBB1B-PWR_BUT-PadP9.9)") (class "Default")
      (node (ref "BBB1") (pin "P9.9") (pinfunction "PWR_BUT_P9.9") (pintype "bidirectional"))
    )
    (net (code "134") (name "unconnected-(BBB1B-SYS_RESET~{N}-PadP9.10)") (class "Default")
      (node (ref "BBB1") (pin "P9.10") (pinfunction "SYS_RESET~{N}_P9.10") (pintype "bidirectional"))
    )
    (net (code "135") (name "unconnected-(BBB1B-VDD_5V-PadP9.5)") (class "Default")
      (node (ref "BBB1") (pin "P9.5") (pinfunction "VDD_5V_P9.5") (pintype "bidirectional"))
    )
    (net (code "136") (name "unconnected-(BBB1B-VDD_5V-PadP9.6)") (class "Default")
      (node (ref "BBB1") (pin "P9.6") (pinfunction "VDD_5V_P9.6") (pintype "bidirectional"))
    )
    (net (code "137") (name "unconnected-(BBB1B-VDD_ADC-PadP9.32)") (class "Default")
      (node (ref "BBB1") (pin "P9.32") (pinfunction "VDD_ADC_P9.32") (pintype "bidirectional"))
    )
    (net (code "138") (name "unconnected-(J5-ID-Pad4)") (class "Default")
      (node (ref "J5") (pin "4") (pinfunction "ID_4") (pintype "passive"))
    )
    (net (code "139") (name "unconnected-(U2-NC-Pad5)") (class "Default")
      (node (ref "U2") (pin "5") (pinfunction "NC_5") (pintype "no_connect"))
    )
    (net (code "140") (name "unconnected-(U2-NC-Pad21)") (class "Default")
      (node (ref "U2") (pin "21") (pinfunction "NC_21") (pintype "no_connect"))
    )
    (net (code "141") (name "unconnected-(U2-NC-Pad22)") (class "Default")
      (node (ref "U2") (pin "22") (pinfunction "NC_22") (pintype "no_connect"))
    )
    (net (code "142") (name "unconnected-(U2-NC-Pad23)") (class "Default")
      (node (ref "U2") (pin "23") (pinfunction "NC_23") (pintype "no_connect"))
    )
    (net (code "143") (name "unconnected-(U2-RESERVED-Pad12)") (class "Default")
      (node (ref "U2") (pin "12") (pinfunction "RESERVED_12") (pintype "input"))
    )
    (net (code "144") (name "unconnected-(U2-SCL2-Pad2)") (class "Default")
      (node (ref "U2") (pin "2") (pinfunction "SCL2_2") (pintype "open_collector"))
    )
    (net (code "145") (name "unconnected-(U2-SDA2-Pad1)") (class "Default")
      (node (ref "U2") (pin "1") (pinfunction "SDA2_1") (pintype "open_collector"))
    )
    (net (code "146") (name "unconnected-(U2-USDB_DM-Pad25)") (class "Default")
      (node (ref "U2") (pin "25") (pinfunction "USDB_DM_25") (pintype "bidirectional"))
    )
    (net (code "147") (name "unconnected-(U2-USDB_DP-Pad26)") (class "Default")
      (node (ref "U2") (pin "26") (pinfunction "USDB_DP_26") (pintype "bidirectional"))
    )
    (net (code "148") (name "unconnected-(U2-~{AADET_N}-Pad20)") (class "Default")
      (node (ref "U2") (pin "20") (pinfunction "~{AADET_N}_20") (pintype "input"))
    )
    (net (code "149") (name "unconnected-(U2-~{RESET_N}-Pad10)") (class "Default")
      (node (ref "U2") (pin "10") (pinfunction "~{RESET_N}_10") (pintype "open_collector"))
    )
    (net (code "150") (name "unconnected-(U3-PA8-Pad41)") (class "Default")
      (node (ref "U3") (pin "41") (pinfunction "PA8_41") (pintype "bidirectional"))
    )
    (net (code "151") (name "unconnected-(U3-PB2-Pad28)") (class "Default")
      (node (ref "U3") (pin "28") (pinfunction "PB2_28") (pintype "bidirectional"))
    )
    (net (code "152") (name "unconnected-(U3-PB4-Pad56)") (class "Default")
      (node (ref "U3") (pin "56") (pinfunction "PB4_56") (pintype "bidirectional"))
    )
    (net (code "153") (name "unconnected-(U3-PB5-Pad57)") (class "Default")
      (node (ref "U3") (pin "57") (pinfunction "PB5_57") (pintype "bidirectional"))
    )
    (net (code "154") (name "unconnected-(U3-PB6-Pad58)") (class "Default")
      (node (ref "U3") (pin "58") (pinfunction "PB6_58") (pintype "bidirectional"))
    )
    (net (code "155") (name "unconnected-(U3-PB7-Pad59)") (class "Default")
      (node (ref "U3") (pin "59") (pinfunction "PB7_59") (pintype "bidirectional"))
    )
    (net (code "156") (name "unconnected-(U3-PB8-Pad61)") (class "Default")
      (node (ref "U3") (pin "61") (pinfunction "PB8_61") (pintype "bidirectional"))
    )
    (net (code "157") (name "unconnected-(U3-PB9-Pad62)") (class "Default")
      (node (ref "U3") (pin "62") (pinfunction "PB9_62") (pintype "bidirectional"))
    )
    (net (code "158") (name "unconnected-(U3-PB12-Pad33)") (class "Default")
      (node (ref "U3") (pin "33") (pinfunction "PB12_33") (pintype "bidirectional"))
    )
    (net (code "159") (name "unconnected-(U3-PB13-Pad34)") (class "Default")
      (node (ref "U3") (pin "34") (pinfunction "PB13_34") (pintype "bidirectional"))
    )
    (net (code "160") (name "unconnected-(U3-PC0-Pad8)") (class "Default")
      (node (ref "U3") (pin "8") (pinfunction "PC0_8") (pintype "bidirectional"))
    )
    (net (code "161") (name "unconnected-(U3-PC1-Pad9)") (class "Default")
      (node (ref "U3") (pin "9") (pinfunction "PC1_9") (pintype "bidirectional"))
    )
    (net (code "162") (name "unconnected-(U3-PC2-Pad10)") (class "Default")
      (node (ref "U3") (pin "10") (pinfunction "PC2_10") (pintype "bidirectional"))
    )
    (net (code "163") (name "unconnected-(U3-PC3-Pad11)") (class "Default")
      (node (ref "U3") (pin "11") (pinfunction "PC3_11") (pintype "bidirectional"))
    )
    (net (code "164") (name "unconnected-(U3-PC7-Pad38)") (class "Default")
      (node (ref "U3") (pin "38") (pinfunction "PC7_38") (pintype "bidirectional"))
    )
    (net (code "165") (name "unconnected-(U3-PC8-Pad39)") (class "Default")
      (node (ref "U3") (pin "39") (pinfunction "PC8_39") (pintype "bidirectional"))
    )
    (net (code "166") (name "unconnected-(U3-PC9-Pad40)") (class "Default")
      (node (ref "U3") (pin "40") (pinfunction "PC9_40") (pintype "bidirectional"))
    )
    (net (code "167") (name "unconnected-(U3-PC10-Pad51)") (class "Default")
      (node (ref "U3") (pin "51") (pinfunction "PC10_51") (pintype "bidirectional"))
    )
    (net (code "168") (name "unconnected-(U3-PC11-Pad52)") (class "Default")
      (node (ref "U3") (pin "52") (pinfunction "PC11_52") (pintype "bidirectional"))
    )
    (net (code "169") (name "unconnected-(U3-PC12-Pad53)") (class "Default")
      (node (ref "U3") (pin "53") (pinfunction "PC12_53") (pintype "bidirectional"))
    )
    (net (code "170") (name "unconnected-(U3-PC13-Pad2)") (class "Default")
      (node (ref "U3") (pin "2") (pinfunction "PC13_2") (pintype "bidirectional"))
    )
    (net (code "171") (name "unconnected-(U3-PC14{slash}OSC32_IN-Pad3)") (class "Default")
      (node (ref "U3") (pin "3") (pinfunction "PC14/OSC32_IN_3") (pintype "bidirectional"))
    )
    (net (code "172") (name "unconnected-(U3-PC15{slash}OSC32_OUT-Pad4)") (class "Default")
      (node (ref "U3") (pin "4") (pinfunction "PC15/OSC32_OUT_4") (pintype "bidirectional"))
    )
    (net (code "173") (name "unconnected-(U3-PD2-Pad54)") (class "Default")
      (node (ref "U3") (pin "54") (pinfunction "PD2_54") (pintype "bidirectional"))
    )
    (net (code "174") (name "unconnected-(U3-PH1{slash}OSC_OUT-Pad6)") (class "Default")
      (node (ref "U3") (pin "6") (pinfunction "PH1/OSC_OUT_6") (pintype "bidirectional"))
    )
  )
)
